# SCH_host-rev-2_0_2025-11-23.net
KiCad netlist of a schematic drawn in EasyEDA
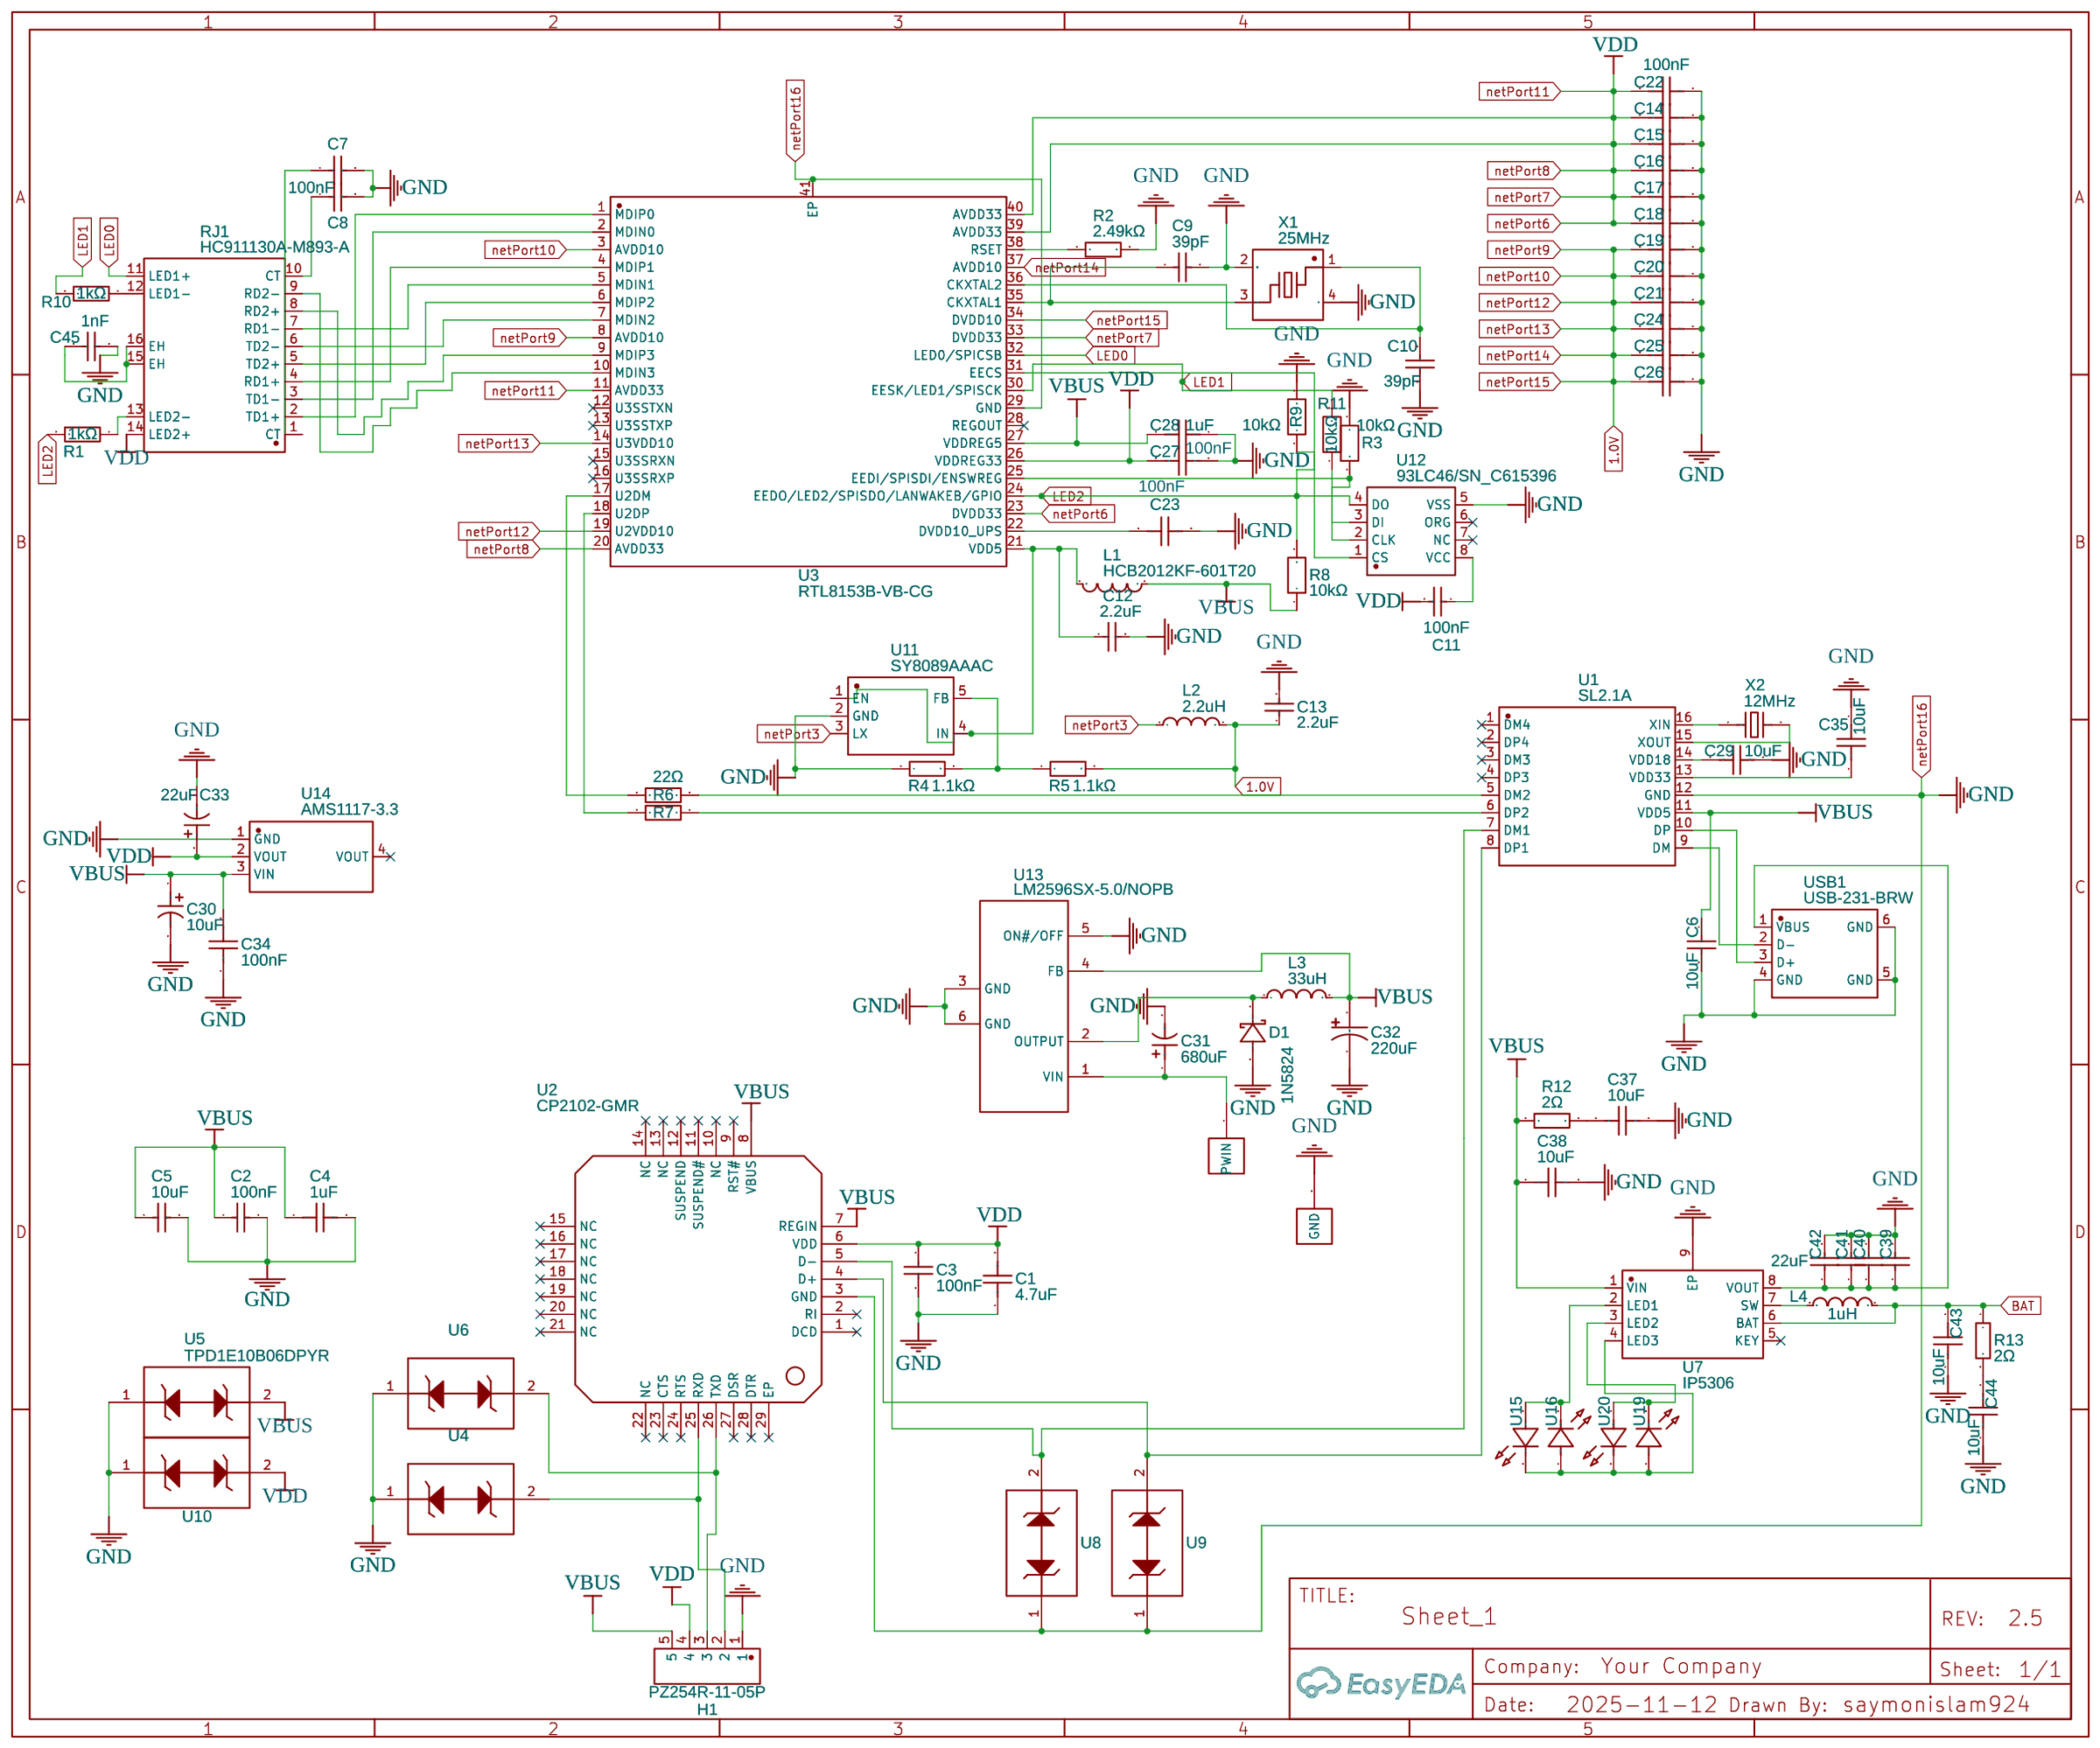
[diagram p0: schematic sheet]

(export (version "E")
  (design (tool "Eeschema 10.0.6"))
  (components
    (comp (ref "C1")
      (value "4.7uF")
      (fields (field (name "Manufacturer Part") "0402X475K100NT") (field (name "Manufacturer") "FH(风华)"))
      (libsource (lib "") (part "0402X475K100NT"))
    )
    (comp (ref "C2")
      (value "100nF")
      (fields (field (name "Manufacturer Part") "0402B104K160NT") (field (name "Manufacturer") "FH(风华)"))
      (libsource (lib "") (part "0402B104K160NT"))
    )
    (comp (ref "C3")
      (value "100nF")
      (fields (field (name "Manufacturer Part") "0402B104K160NT") (field (name "Manufacturer") "FH(风华)"))
      (libsource (lib "") (part "0402B104K160NT_1"))
    )
    (comp (ref "C4")
      (value "1uF")
      (fields (field (name "Manufacturer Part") "0402X105M100NT") (field (name "Manufacturer") "FH(风华)"))
      (libsource (lib "") (part "0402X105M100NT"))
    )
    (comp (ref "C5")
      (value "10uF")
      (fields (field (name "Manufacturer Part") "0603X106K100NT") (field (name "Manufacturer") "FH(风华)"))
      (libsource (lib "") (part "0603X106K100NT"))
    )
    (comp (ref "C6")
      (value "10uF")
      (fields (field (name "Manufacturer Part") "1206B106K160NT") (field (name "Manufacturer") "FH(风华)"))
      (libsource (lib "") (part "1206B106K160NT"))
    )
    (comp (ref "C7")
      (value "100nF")
      (fields (field (name "Manufacturer Part") "0402B104K160NT") (field (name "Manufacturer") "FH(风华)"))
      (libsource (lib "") (part "0402B104K160NT"))
    )
    (comp (ref "C8")
      (value "100nF")
      (fields (field (name "Manufacturer Part") "0402B104K160NT") (field (name "Manufacturer") "FH(风华)"))
      (libsource (lib "") (part "0402B104K160NT"))
    )
    (comp (ref "C9")
      (value "39pF")
      (fields (field (name "Manufacturer Part") "0402CG390J500NT") (field (name "Manufacturer") "FH(风华)"))
      (libsource (lib "") (part "0402CG390J500NT_1"))
    )
    (comp (ref "C10")
      (value "39pF")
      (fields (field (name "Manufacturer Part") "0402CG390J500NT") (field (name "Manufacturer") "FH(风华)"))
      (libsource (lib "") (part "0402CG390J500NT"))
    )
    (comp (ref "C11")
      (value "100nF")
      (fields (field (name "Manufacturer Part") "0402B104J160NT") (field (name "Manufacturer") "FH(风华)"))
      (libsource (lib "") (part "0402B104J160NT"))
    )
    (comp (ref "C12")
      (value "2.2uF")
      (fields (field (name "Manufacturer Part") "0402X225K6R3NT") (field (name "Manufacturer") "FH(风华)"))
      (libsource (lib "") (part "0402X225K6R3NT_1"))
    )
    (comp (ref "C13")
      (value "2.2uF")
      (fields (field (name "Manufacturer Part") "0402X225K6R3NT") (field (name "Manufacturer") "FH(风华)"))
      (libsource (lib "") (part "0402X225K6R3NT"))
    )
    (comp (ref "C14")
      (value "100nF")
      (fields
        (field (name "Manufacturer Part") "CC0402KRX5R6BB104")
        (field (name "Manufacturer") "YAGEO(国巨)")
      )
      (libsource (lib "") (part "CC0402KRX5R6BB104"))
    )
    (comp (ref "C15")
      (value "100nF")
      (fields
        (field (name "Manufacturer Part") "CC0402KRX5R6BB104")
        (field (name "Manufacturer") "YAGEO(国巨)")
      )
      (libsource (lib "") (part "CC0402KRX5R6BB104"))
    )
    (comp (ref "C16")
      (value "100nF")
      (fields
        (field (name "Manufacturer Part") "CC0402KRX5R6BB104")
        (field (name "Manufacturer") "YAGEO(国巨)")
      )
      (libsource (lib "") (part "CC0402KRX5R6BB104"))
    )
    (comp (ref "C17")
      (value "100nF")
      (fields
        (field (name "Manufacturer Part") "CC0402KRX5R6BB104")
        (field (name "Manufacturer") "YAGEO(国巨)")
      )
      (libsource (lib "") (part "CC0402KRX5R6BB104"))
    )
    (comp (ref "C18")
      (value "100nF")
      (fields
        (field (name "Manufacturer Part") "CC0402KRX5R6BB104")
        (field (name "Manufacturer") "YAGEO(国巨)")
      )
      (libsource (lib "") (part "CC0402KRX5R6BB104"))
    )
    (comp (ref "C19")
      (value "100nF")
      (fields
        (field (name "Manufacturer Part") "CC0402KRX5R6BB104")
        (field (name "Manufacturer") "YAGEO(国巨)")
      )
      (libsource (lib "") (part "CC0402KRX5R6BB104"))
    )
    (comp (ref "C20")
      (value "100nF")
      (fields
        (field (name "Manufacturer Part") "CC0402KRX5R6BB104")
        (field (name "Manufacturer") "YAGEO(国巨)")
      )
      (libsource (lib "") (part "CC0402KRX5R6BB104"))
    )
    (comp (ref "C21")
      (value "100nF")
      (fields
        (field (name "Manufacturer Part") "CC0402KRX5R6BB104")
        (field (name "Manufacturer") "YAGEO(国巨)")
      )
      (libsource (lib "") (part "CC0402KRX5R6BB104"))
    )
    (comp (ref "C22")
      (value "100nF")
      (fields
        (field (name "Manufacturer Part") "CC0402KRX5R6BB104")
        (field (name "Manufacturer") "YAGEO(国巨)")
      )
      (libsource (lib "") (part "CC0402KRX5R6BB104"))
    )
    (comp (ref "C23")
      (value "100nF")
      (fields
        (field (name "Manufacturer Part") "CC0402KRX5R6BB104")
        (field (name "Manufacturer") "YAGEO(国巨)")
      )
      (libsource (lib "") (part "CC0402KRX5R6BB104"))
    )
    (comp (ref "C24")
      (value "100nF")
      (fields
        (field (name "Manufacturer Part") "CC0402KRX5R6BB104")
        (field (name "Manufacturer") "YAGEO(国巨)")
      )
      (libsource (lib "") (part "CC0402KRX5R6BB104"))
    )
    (comp (ref "C25")
      (value "100nF")
      (fields
        (field (name "Manufacturer Part") "CC0402KRX5R6BB104")
        (field (name "Manufacturer") "YAGEO(国巨)")
      )
      (libsource (lib "") (part "CC0402KRX5R6BB104"))
    )
    (comp (ref "C26")
      (value "100nF")
      (fields
        (field (name "Manufacturer Part") "CC0402KRX5R6BB104")
        (field (name "Manufacturer") "YAGEO(国巨)")
      )
      (libsource (lib "") (part "CC0402KRX5R6BB104"))
    )
    (comp (ref "C27")
      (value "100nF")
      (fields
        (field (name "Manufacturer Part") "CC0402KRX5R6BB104")
        (field (name "Manufacturer") "YAGEO(国巨)")
      )
      (libsource (lib "") (part "CC0402KRX5R6BB104"))
    )
    (comp (ref "C28")
      (value "1uF")
      (fields (field (name "Manufacturer Part") "0402X105K100NT") (field (name "Manufacturer") "FH(风华)"))
      (libsource (lib "") (part "0402X105K100NT"))
    )
    (comp (ref "C29")
      (value "10uF")
      (fields (field (name "Manufacturer Part") "0402X106M6R3NT") (field (name "Manufacturer") "FH(风华)"))
      (libsource (lib "") (part "0402X106M6R3NT_2"))
    )
    (comp (ref "C30")
      (value "10uF")
      (fields
        (field (name "Manufacturer Part") "RVT1E100M0405 10UF 25V")
        (field (name "Manufacturer") "DMBJ(振宝佳)")
      )
      (libsource (lib "") (part "RVT1E100M0405 10UF 25V"))
    )
    (comp (ref "C31")
      (value "680uF")
      (fields
        (field (name "Manufacturer Part") "GVE1E687M1010CN")
        (field (name "Manufacturer") "ACMECON(鼎容)")
      )
      (libsource (lib "") (part "GVE1E687M1010CN"))
    )
    (comp (ref "C32")
      (value "220uF")
      (fields (field (name "Manufacturer Part") "EEETC1V221P") (field (name "Manufacturer") "PANASONIC(松下)"))
      (libsource (lib "") (part "EEETC1V221P"))
    )
    (comp (ref "C33")
      (value "22uF")
      (fields
        (field (name "Manufacturer Part") "CA45-A-10V-22uF-K")
        (field (name "Manufacturer") "TORCH(火炬)")
      )
      (libsource (lib "") (part "CA45-A-10V-22μF-K"))
    )
    (comp (ref "C34")
      (value "100nF")
      (fields
        (field (name "Manufacturer Part") "CT41G-0805-2X1-50V-0.1uF-M(N)")
        (field (name "Manufacturer") "TORCH(火炬)")
      )
      (libsource (lib "") (part "CT41G-0805-2X1-50V-0.1μF-M(N)"))
    )
    (comp (ref "C35")
      (value "10uF")
      (fields (field (name "Manufacturer Part") "0402X106M6R3NT") (field (name "Manufacturer") "FH(风华)"))
      (libsource (lib "") (part "0402X106M6R3NT"))
    )
    (comp (ref "C37")
      (value "10uF")
      (fields (field (name "Manufacturer Part") "0402X106M6R3NT") (field (name "Manufacturer") "FH(风华)"))
      (libsource (lib "") (part "0402X106M6R3NT_2"))
    )
    (comp (ref "C38")
      (value "10uF")
      (fields (field (name "Manufacturer Part") "0402X106M6R3NT") (field (name "Manufacturer") "FH(风华)"))
      (libsource (lib "") (part "0402X106M6R3NT_2"))
    )
    (comp (ref "C39")
      (value "22uF")
      (fields (field (name "Manufacturer Part") "1206X226K100NT") (field (name "Manufacturer") "FH(风华)"))
      (libsource (lib "") (part "1206X226K100NT"))
    )
    (comp (ref "C40")
      (value "22uF")
      (fields (field (name "Manufacturer Part") "1206X226K100NT") (field (name "Manufacturer") "FH(风华)"))
      (libsource (lib "") (part "1206X226K100NT"))
    )
    (comp (ref "C41")
      (value "22uF")
      (fields (field (name "Manufacturer Part") "1206X226K100NT") (field (name "Manufacturer") "FH(风华)"))
      (libsource (lib "") (part "1206X226K100NT"))
    )
    (comp (ref "C42")
      (value "22uF")
      (fields (field (name "Manufacturer Part") "1206X226K100NT") (field (name "Manufacturer") "FH(风华)"))
      (libsource (lib "") (part "1206X226K100NT"))
    )
    (comp (ref "C43")
      (value "10uF")
      (fields (field (name "Manufacturer Part") "0402X106M6R3NT") (field (name "Manufacturer") "FH(风华)"))
      (libsource (lib "") (part "0402X106M6R3NT_1"))
    )
    (comp (ref "C44")
      (value "10uF")
      (fields (field (name "Manufacturer Part") "0402X106M6R3NT") (field (name "Manufacturer") "FH(风华)"))
      (libsource (lib "") (part "0402X106M6R3NT_1"))
    )
    (comp (ref "C45")
      (value "1nF")
      (fields (field (name "Manufacturer Part") "1206B102K202NT") (field (name "Manufacturer") "FH(风华)"))
      (libsource (lib "") (part "1206B102K202NT"))
    )
    (comp (ref "D1")
      (value "1N5824")
      (fields (field (name "Manufacturer") "FUXINSEMI(富芯森美)"))
      (libsource (lib "") (part "1N5824_C7503125"))
    )
    (comp (ref "H1")
      (value "PZ254R-11-05P")
      (fields (field (name "Manufacturer") "XFCN(兴飞)"))
      (libsource (lib "") (part "PZ254R-11-05P"))
    )
    (comp (ref "L1")
      (value "HCB2012KF-601T20")
      (fields (field (name "Manufacturer") "TAI-TECH(台庆)"))
      (libsource (lib "") (part "HCB2012KF-601T20"))
    )
    (comp (ref "L2")
      (value "2.2uH")
      (fields (field (name "Manufacturer Part") "ANR3015T2R2M") (field (name "Manufacturer") "APV(爱普微)"))
      (libsource (lib "") (part "ANR3015T2R2M"))
    )
    (comp (ref "L3")
      (value "33uH")
      (fields (field (name "Manufacturer Part") "SMDRS1275-330N") (field (name "Manufacturer") "SXN(顺翔诺)"))
      (libsource (lib "") (part "SMDRS1275-330N"))
    )
    (comp (ref "L4")
      (value "1uH")
      (fields (field (name "Manufacturer Part") "PRS3015-1R0NT") (field (name "Manufacturer") "FH(风华)"))
      (libsource (lib "") (part "PRS3015-1R0NT"))
    )
    (comp (ref "R1")
      (value "1kΩ")
      (fields (field (name "Manufacturer Part") "RC-02K1001FT") (field (name "Manufacturer") "FH(风华)"))
      (libsource (lib "") (part "RC-02K1001FT"))
    )
    (comp (ref "R2")
      (value "2.49kΩ")
      (fields (field (name "Manufacturer Part") "RC-02K2491FT") (field (name "Manufacturer") "FH(风华)"))
      (libsource (lib "") (part "RC-02K2491FT"))
    )
    (comp (ref "R3")
      (value "10kΩ")
      (fields (field (name "Manufacturer Part") "RC-02K103JT") (field (name "Manufacturer") "FH(风华)"))
      (libsource (lib "") (part "RC-02K103JT"))
    )
    (comp (ref "R4")
      (value "1.1kΩ")
      (fields (field (name "Manufacturer Part") "RC-02K1101FT") (field (name "Manufacturer") "FH(风华)"))
      (libsource (lib "") (part "RC-02K1101FT"))
    )
    (comp (ref "R5")
      (value "1.1kΩ")
      (fields (field (name "Manufacturer Part") "RC-02K1101FT") (field (name "Manufacturer") "FH(风华)"))
      (libsource (lib "") (part "RC-02K1101FT"))
    )
    (comp (ref "R6")
      (value "22Ω")
      (fields (field (name "Manufacturer Part") "RC-02K22R0FT") (field (name "Manufacturer") "FH(风华)"))
      (libsource (lib "") (part "RC-02K22R0FT"))
    )
    (comp (ref "R7")
      (value "22Ω")
      (fields (field (name "Manufacturer Part") "RC-02K22R0FT") (field (name "Manufacturer") "FH(风华)"))
      (libsource (lib "") (part "RC-02K22R0FT"))
    )
    (comp (ref "R8")
      (value "10kΩ")
      (fields (field (name "Manufacturer Part") "RC-02K103JT") (field (name "Manufacturer") "FH(风华)"))
      (libsource (lib "") (part "RC-02K103JT"))
    )
    (comp (ref "R9")
      (value "10kΩ")
      (fields (field (name "Manufacturer Part") "RC-02K103JT") (field (name "Manufacturer") "FH(风华)"))
      (libsource (lib "") (part "RC-02K103JT"))
    )
    (comp (ref "R10")
      (value "1kΩ")
      (fields (field (name "Manufacturer Part") "RC-02K1001FT") (field (name "Manufacturer") "FH(风华)"))
      (libsource (lib "") (part "RC-02K1001FT"))
    )
    (comp (ref "R11")
      (value "10kΩ")
      (fields (field (name "Manufacturer Part") "RC-02K103JT") (field (name "Manufacturer") "FH(风华)"))
      (libsource (lib "") (part "RC-02K103JT"))
    )
    (comp (ref "R12")
      (value "2Ω")
      (fields (field (name "Manufacturer Part") "RS-03L2R00FT") (field (name "Manufacturer") "FH(风华)"))
      (libsource (lib "") (part "RS-03L2R00FT_1"))
    )
    (comp (ref "R13")
      (value "2Ω")
      (fields (field (name "Manufacturer Part") "RS-03L2R00FT") (field (name "Manufacturer") "FH(风华)"))
      (libsource (lib "") (part "RS-03L2R00FT"))
    )
    (comp (ref "RJ1")
      (value "HC911130A-M893-A")
      (fields
        (field (name "Manufacturer Part") "HC612601A-M893-A")
        (field (name "Manufacturer") "HCTL(华灿天禄)")
      )
      (libsource (lib "") (part "HC911130A-M893-A"))
    )
    (comp (ref "U1")
      (value "SL2.1A")
      (fields (field (name "Manufacturer") "CoreChips(和芯润德)"))
      (libsource (lib "") (part "SL2.1A"))
    )
    (comp (ref "U2")
      (value "CP2102-GMR")
      (fields (field (name "Manufacturer") "SKYWORKS/SILICON LABS(芯科)"))
      (libsource (lib "") (part "CP2102-GMR"))
    )
    (comp (ref "U3")
      (value "RTL8153B-VB-CG")
      (fields (field (name "Manufacturer") "REALTEK(瑞昱)"))
      (libsource (lib "") (part "RTL8153B-VB-CG"))
    )
    (comp (ref "U4")
      (value "TPD1E10B06DPYR")
      (fields (field (name "Manufacturer") "TI(德州仪器)"))
      (libsource (lib "") (part "TPD1E10B06DPYR"))
    )
    (comp (ref "U5")
      (value "TPD1E10B06DPYR")
      (fields (field (name "Manufacturer") "TI(德州仪器)"))
      (libsource (lib "") (part "TPD1E10B06DPYR"))
    )
    (comp (ref "U6")
      (value "TPD1E10B06DPYR")
      (fields (field (name "Manufacturer") "TI(德州仪器)"))
      (libsource (lib "") (part "TPD1E10B06DPYR"))
    )
    (comp (ref "U7")
      (value "IP5306")
      (fields (field (name "Manufacturer") "INJOINIC(英集芯)"))
      (libsource (lib "") (part "IP5306"))
    )
    (comp (ref "U8")
      (value "TPD1E10B06DPYR")
      (fields (field (name "Manufacturer") "TI(德州仪器)"))
      (libsource (lib "") (part "TPD1E10B06DPYR_1"))
    )
    (comp (ref "U9")
      (value "TPD1E10B06DPYR")
      (fields (field (name "Manufacturer") "TI(德州仪器)"))
      (libsource (lib "") (part "TPD1E10B06DPYR_1"))
    )
    (comp (ref "U10")
      (value "TPD1E10B06DPYR")
      (fields (field (name "Manufacturer") "TI(德州仪器)"))
      (libsource (lib "") (part "TPD1E10B06DPYR"))
    )
    (comp (ref "U11")
      (value "SY8089AAAC")
      (fields (field (name "Manufacturer") "Silergy(矽力杰)"))
      (libsource (lib "") (part "SY8089AAAC"))
    )
    (comp (ref "U12")
      (value "93LC46/SN_C615396")
      (fields (field (name "Manufacturer Part") "93LC46/SN") (field (name "Manufacturer") "MICROCHIP(美国微芯)"))
      (libsource (lib "") (part "93LC46/SN_C615396"))
    )
    (comp (ref "U13")
      (value "LM2596SX-5.0/NOPB")
      (fields (field (name "Manufacturer") "TI(德州仪器)"))
      (libsource (lib "") (part "LM2596SX-5.0/NOPB"))
    )
    (comp (ref "U14")
      (value "AMS1117-3.3")
      (fields (field (name "Manufacturer") "AMS"))
      (libsource (lib "") (part "AMS1117-3.3"))
    )
    (comp (ref "U15")
      (value "XL-3216UWC")
      (fields (field (name "Manufacturer") "XINGLIGHT(成兴光)"))
      (libsource (lib "") (part "XL-3216UWC_1"))
    )
    (comp (ref "U16")
      (value "XL-3216UWC")
      (fields (field (name "Manufacturer") "XINGLIGHT(成兴光)"))
      (libsource (lib "") (part "XL-3216UWC"))
    )
    (comp (ref "U19")
      (value "XL-3216UWC")
      (fields (field (name "Manufacturer") "XINGLIGHT(成兴光)"))
      (libsource (lib "") (part "XL-3216UWC"))
    )
    (comp (ref "U20")
      (value "XL-3216UWC")
      (fields (field (name "Manufacturer") "XINGLIGHT(成兴光)"))
      (libsource (lib "") (part "XL-3216UWC_1"))
    )
    (comp (ref "U24") (value "Test-Pad") (libsource (lib "") (part "Test-Pad")))
    (comp (ref "U25") (value "Test-Pad") (libsource (lib "") (part "Test-Pad_1")))
    (comp (ref "USB1")
      (value "USB-231-BRW")
      (fields (field (name "Manufacturer") "XUNPU(讯普)"))
      (libsource (lib "") (part "USB-231-BRW"))
    )
    (comp (ref "X1")
      (value "25MHz")
      (fields
        (field (name "Manufacturer Part") "XXHCCLNANF-25.000000")
        (field (name "Manufacturer") "TAITIEN(泰艺电子)")
      )
      (libsource (lib "") (part "XXHCCLNANF-25.000000"))
    )
    (comp (ref "X2")
      (value "12MHz")
      (fields
        (field (name "Manufacturer Part") "S47SMD12.000M20PF20R30B3")
        (field (name "Manufacturer") "SOSET(索斯特)")
      )
      (libsource (lib "") (part "S47SMD12.000M20PF20R30B3"))
    )
  )
  (nets
    (net (code "1") (name "1.0V") (class "Default")
      (node (ref "C13") (pin "1") (pinfunction "1_1") (pintype "input"))
      (node (ref "C19") (pin "1") (pinfunction "1_1") (pintype "unspecified"))
      (node (ref "C20") (pin "1") (pinfunction "1_1") (pintype "unspecified"))
      (node (ref "C21") (pin "1") (pinfunction "1_1") (pintype "unspecified"))
      (node (ref "C24") (pin "1") (pinfunction "1_1") (pintype "unspecified"))
      (node (ref "C25") (pin "1") (pinfunction "1_1") (pintype "unspecified"))
      (node (ref "C26") (pin "1") (pinfunction "1_1") (pintype "unspecified"))
      (node (ref "L2") (pin "2") (pinfunction "2_2") (pintype "unspecified"))
      (node (ref "R5") (pin "2") (pinfunction "2_2") (pintype "unspecified"))
      (node (ref "U3") (pin "14") (pinfunction "U3VDD10_14") (pintype "unspecified"))
      (node (ref "U3") (pin "19") (pinfunction "U2VDD10_19") (pintype "unspecified"))
      (node (ref "U3") (pin "3") (pinfunction "AVDD10_3") (pintype "unspecified"))
      (node (ref "U3") (pin "34") (pinfunction "DVDD10_34") (pintype "unspecified"))
      (node (ref "U3") (pin "37") (pinfunction "AVDD10_37") (pintype "unspecified"))
      (node (ref "U3") (pin "8") (pinfunction "AVDD10_8") (pintype "unspecified"))
    )
    (net (code "2") (name "BAT") (class "Default")
      (node (ref "C43") (pin "2") (pinfunction "2_2") (pintype "unspecified"))
      (node (ref "L4") (pin "1") (pinfunction "1_1") (pintype "unspecified"))
      (node (ref "R13") (pin "1") (pinfunction "1_1") (pintype "unspecified"))
      (node (ref "U7") (pin "6") (pinfunction "BAT_6") (pintype "unspecified"))
    )
    (net (code "3") (name "LED0") (class "Default")
      (node (ref "RJ1") (pin "11") (pinfunction "LED1+_11") (pintype "unspecified"))
      (node (ref "U3") (pin "32") (pinfunction "LED0/SPICSB_32") (pintype "unspecified"))
    )
    (net (code "4") (name "LED1") (class "Default")
      (node (ref "R10") (pin "2") (pinfunction "2_2") (pintype "unspecified"))
      (node (ref "R11") (pin "2") (pinfunction "2_2") (pintype "unspecified"))
      (node (ref "U3") (pin "30") (pinfunction "EESK/LED1/SPISCK_30") (pintype "unspecified"))
    )
    (net (code "5") (name "LED2") (class "Default")
      (node (ref "R1") (pin "2") (pinfunction "2_2") (pintype "unspecified"))
      (node (ref "R8") (pin "2") (pinfunction "2_2") (pintype "unspecified"))
      (node (ref "R9") (pin "1") (pinfunction "1_1") (pintype "unspecified"))
      (node (ref "U12") (pin "4") (pinfunction "DO_4") (pintype "unspecified"))
      (node (ref "U3") (pin "24") (pinfunction "EEDO/LED2/SPISDO/LANWAKEB/GPIO_24") (pintype "unspecified"))
    )
    (net (code "6") (name "Net-(C7-Pad1)") (class "Default")
      (node (ref "C7") (pin "1") (pinfunction "1_1") (pintype "input"))
      (node (ref "RJ1") (pin "1") (pinfunction "CT_1") (pintype "unspecified"))
    )
    (net (code "7") (name "Net-(C8-Pad1)") (class "Default")
      (node (ref "C8") (pin "1") (pinfunction "1_1") (pintype "input"))
      (node (ref "RJ1") (pin "10") (pinfunction "CT_10") (pintype "unspecified"))
    )
    (net (code "8") (name "Net-(C37-Pad2)") (class "Default")
      (node (ref "C37") (pin "2") (pinfunction "2_2") (pintype "unspecified"))
      (node (ref "R12") (pin "2") (pinfunction "2_2") (pintype "unspecified"))
    )
    (net (code "9") (name "Net-(C44-Pad2)") (class "Default")
      (node (ref "C44") (pin "2") (pinfunction "2_2") (pintype "unspecified"))
      (node (ref "R13") (pin "2") (pinfunction "2_2") (pintype "unspecified"))
    )
    (net (code "10") (name "Net-(C45-Pad1)") (class "Default")
      (node (ref "C45") (pin "1") (pinfunction "1_1") (pintype "input"))
      (node (ref "RJ1") (pin "15") (pinfunction "EH_15") (pintype "unspecified"))
      (node (ref "RJ1") (pin "16") (pinfunction "EH_16") (pintype "unspecified"))
    )
    (net (code "11") (name "Net-(D1-K)") (class "Default")
      (node (ref "D1") (pin "1") (pinfunction "K_1") (pintype "unspecified"))
      (node (ref "L3") (pin "1") (pinfunction "1_1") (pintype "unspecified"))
      (node (ref "U13") (pin "2") (pinfunction "OUTPUT_2") (pintype "unspecified"))
    )
    (net (code "12") (name "Net-(RJ1-LED1-)") (class "Default")
      (node (ref "R10") (pin "1") (pinfunction "1_1") (pintype "unspecified"))
      (node (ref "RJ1") (pin "12") (pinfunction "LED1-_12") (pintype "unspecified"))
    )
    (net (code "13") (name "Net-(RJ1-LED2-)") (class "Default")
      (node (ref "R1") (pin "1") (pinfunction "1_1") (pintype "unspecified"))
      (node (ref "RJ1") (pin "13") (pinfunction "LED2-_13") (pintype "unspecified"))
    )
    (net (code "14") (name "Net-(RJ1-RD1+)") (class "Default")
      (node (ref "RJ1") (pin "4") (pinfunction "RD1+_4") (pintype "unspecified"))
      (node (ref "U3") (pin "4") (pinfunction "MDIP1_4") (pintype "unspecified"))
    )
    (net (code "15") (name "Net-(RJ1-RD1-)") (class "Default")
      (node (ref "RJ1") (pin "7") (pinfunction "RD1-_7") (pintype "unspecified"))
      (node (ref "U3") (pin "5") (pinfunction "MDIN1_5") (pintype "unspecified"))
    )
    (net (code "16") (name "Net-(RJ1-RD2+)") (class "Default")
      (node (ref "RJ1") (pin "8") (pinfunction "RD2+_8") (pintype "unspecified"))
      (node (ref "U3") (pin "9") (pinfunction "MDIP3_9") (pintype "unspecified"))
    )
    (net (code "17") (name "Net-(RJ1-RD2-)") (class "Default")
      (node (ref "RJ1") (pin "9") (pinfunction "RD2-_9") (pintype "unspecified"))
      (node (ref "U3") (pin "10") (pinfunction "MDIN3_10") (pintype "unspecified"))
    )
    (net (code "18") (name "Net-(RJ1-TD1+)") (class "Default")
      (node (ref "RJ1") (pin "2") (pinfunction "TD1+_2") (pintype "unspecified"))
      (node (ref "U3") (pin "1") (pinfunction "MDIP0_1") (pintype "unspecified"))
    )
    (net (code "19") (name "Net-(RJ1-TD1-)") (class "Default")
      (node (ref "RJ1") (pin "3") (pinfunction "TD1-_3") (pintype "unspecified"))
      (node (ref "U3") (pin "2") (pinfunction "MDIN0_2") (pintype "unspecified"))
    )
    (net (code "20") (name "Net-(RJ1-TD2+)") (class "Default")
      (node (ref "RJ1") (pin "5") (pinfunction "TD2+_5") (pintype "unspecified"))
      (node (ref "U3") (pin "6") (pinfunction "MDIP2_6") (pintype "unspecified"))
    )
    (net (code "21") (name "Net-(RJ1-TD2-)") (class "Default")
      (node (ref "RJ1") (pin "6") (pinfunction "TD2-_6") (pintype "unspecified"))
      (node (ref "U3") (pin "7") (pinfunction "MDIN2_7") (pintype "unspecified"))
    )
    (net (code "22") (name "Net-(U1-DM)") (class "Default")
      (node (ref "U1") (pin "9") (pinfunction "DM_9") (pintype "unspecified"))
      (node (ref "USB1") (pin "2") (pinfunction "D-_2") (pintype "unspecified"))
    )
    (net (code "23") (name "Net-(U1-DM1)") (class "Default")
      (node (ref "U1") (pin "7") (pinfunction "DM1_7") (pintype "unspecified"))
      (node (ref "U2") (pin "5") (pinfunction "D-_5") (pintype "unspecified"))
      (node (ref "U8") (pin "2") (pintype "bidirectional"))
    )
    (net (code "24") (name "Net-(U1-DM2)") (class "Default")
      (node (ref "R6") (pin "1") (pinfunction "1_1") (pintype "unspecified"))
      (node (ref "U1") (pin "5") (pinfunction "DM2_5") (pintype "unspecified"))
    )
    (net (code "25") (name "Net-(U1-DP)") (class "Default")
      (node (ref "U1") (pin "10") (pinfunction "DP_10") (pintype "unspecified"))
      (node (ref "USB1") (pin "3") (pinfunction "D+_3") (pintype "unspecified"))
    )
    (net (code "26") (name "Net-(U1-DP1)") (class "Default")
      (node (ref "U1") (pin "8") (pinfunction "DP1_8") (pintype "unspecified"))
      (node (ref "U2") (pin "4") (pinfunction "D+_4") (pintype "unspecified"))
      (node (ref "U9") (pin "2") (pintype "bidirectional"))
    )
    (net (code "27") (name "Net-(U1-DP2)") (class "Default")
      (node (ref "R7") (pin "1") (pinfunction "1_1") (pintype "unspecified"))
      (node (ref "U1") (pin "6") (pinfunction "DP2_6") (pintype "unspecified"))
    )
    (net (code "28") (name "Net-(U1-VDD18)") (class "Default")
      (node (ref "C29") (pin "2") (pinfunction "2_2") (pintype "unspecified"))
      (node (ref "U1") (pin "14") (pinfunction "VDD18_14") (pintype "unspecified"))
    )
    (net (code "29") (name "Net-(U1-VDD33)") (class "Default")
      (node (ref "C35") (pin "2") (pinfunction "2_2") (pintype "unspecified"))
      (node (ref "U1") (pin "13") (pinfunction "VDD33_13") (pintype "unspecified"))
    )
    (net (code "30") (name "Net-(U1-XIN)") (class "Default")
      (node (ref "U1") (pin "16") (pinfunction "XIN_16") (pintype "unspecified"))
      (node (ref "X2") (pin "1") (pinfunction "1_1") (pintype "input"))
    )
    (net (code "31") (name "Net-(U1-XOUT)") (class "Default")
      (node (ref "U1") (pin "15") (pinfunction "XOUT_15") (pintype "unspecified"))
      (node (ref "X2") (pin "2") (pinfunction "2_2") (pintype "input"))
    )
    (net (code "32") (name "Net-(U2-RXD)") (class "Default")
      (node (ref "H1") (pin "2") (pinfunction "2_2") (pintype "unspecified"))
      (node (ref "U2") (pin "25") (pinfunction "RXD_25") (pintype "unspecified"))
      (node (ref "U4") (pin "2") (pintype "bidirectional"))
    )
    (net (code "33") (name "Net-(U2-TXD)") (class "Default")
      (node (ref "H1") (pin "3") (pinfunction "3_3") (pintype "unspecified"))
      (node (ref "U2") (pin "26") (pinfunction "TXD_26") (pintype "unspecified"))
      (node (ref "U6") (pin "2") (pintype "bidirectional"))
    )
    (net (code "34") (name "Net-(U3-CKXTAL1)") (class "Default")
      (node (ref "C9") (pin "1") (pinfunction "1_1") (pintype "input"))
      (node (ref "U3") (pin "35") (pinfunction "CKXTAL1_35") (pintype "unspecified"))
      (node (ref "X1") (pin "3") (pinfunction "3_3") (pintype "input"))
    )
    (net (code "35") (name "Net-(U3-CKXTAL2)") (class "Default")
      (node (ref "C10") (pin "1") (pinfunction "1_1") (pintype "input"))
      (node (ref "U3") (pin "36") (pinfunction "CKXTAL2_36") (pintype "unspecified"))
      (node (ref "X1") (pin "1") (pinfunction "1_1") (pintype "input"))
    )
    (net (code "36") (name "Net-(U3-DVDD10_UPS)") (class "Default")
      (node (ref "C23") (pin "1") (pinfunction "1_1") (pintype "unspecified"))
      (node (ref "U3") (pin "22") (pinfunction "DVDD10_UPS_22") (pintype "unspecified"))
    )
    (net (code "37") (name "Net-(U3-RSET)") (class "Default")
      (node (ref "R2") (pin "1") (pinfunction "1_1") (pintype "unspecified"))
      (node (ref "U3") (pin "38") (pinfunction "RSET_38") (pintype "unspecified"))
    )
    (net (code "38") (name "Net-(U3-U2DM)") (class "Default")
      (node (ref "R6") (pin "2") (pinfunction "2_2") (pintype "unspecified"))
      (node (ref "U3") (pin "17") (pinfunction "U2DM_17") (pintype "unspecified"))
    )
    (net (code "39") (name "Net-(U3-U2DP)") (class "Default")
      (node (ref "R7") (pin "2") (pinfunction "2_2") (pintype "unspecified"))
      (node (ref "U3") (pin "18") (pinfunction "U2DP_18") (pintype "unspecified"))
    )
    (net (code "40") (name "Net-(U7-SW)") (class "Default")
      (node (ref "L4") (pin "2") (pinfunction "2_2") (pintype "unspecified"))
      (node (ref "U7") (pin "7") (pinfunction "SW_7") (pintype "unspecified"))
    )
    (net (code "41") (name "Net-(U7-VOUT)") (class "Default")
      (node (ref "C39") (pin "1") (pinfunction "1_1") (pintype "input"))
      (node (ref "C40") (pin "1") (pinfunction "1_1") (pintype "input"))
      (node (ref "C41") (pin "1") (pinfunction "1_1") (pintype "input"))
      (node (ref "C42") (pin "1") (pinfunction "1_1") (pintype "input"))
      (node (ref "U7") (pin "8") (pinfunction "VOUT_8") (pintype "unspecified"))
      (node (ref "USB1") (pin "1") (pinfunction "VBUS_1") (pintype "unspecified"))
    )
    (net (code "42") (name "Net-(U11-EN)") (class "Default")
      (node (ref "C12") (pin "1") (pinfunction "1_1") (pintype "input"))
      (node (ref "L1") (pin "2") (pinfunction "2_2") (pintype "unspecified"))
      (node (ref "U11") (pin "1") (pinfunction "EN_1") (pintype "unspecified"))
      (node (ref "U11") (pin "4") (pinfunction "IN_4") (pintype "unspecified"))
      (node (ref "U3") (pin "21") (pinfunction "VDD5_21") (pintype "unspecified"))
    )
    (net (code "43") (name "Net-(U11-FB)") (class "Default")
      (node (ref "R4") (pin "2") (pinfunction "2_2") (pintype "unspecified"))
      (node (ref "R5") (pin "1") (pinfunction "1_1") (pintype "unspecified"))
      (node (ref "U11") (pin "5") (pinfunction "FB_5") (pintype "unspecified"))
    )
    (net (code "44") (name "Net-(U12-CLK)") (class "Default")
      (node (ref "R11") (pin "1") (pinfunction "1_1") (pintype "unspecified"))
      (node (ref "U12") (pin "2") (pinfunction "CLK_2") (pintype "unspecified"))
    )
    (net (code "45") (name "Net-(U12-CS)") (class "Default")
      (node (ref "U12") (pin "1") (pinfunction "CS_1") (pintype "unspecified"))
      (node (ref "U3") (pin "31") (pinfunction "EECS_31") (pintype "unspecified"))
    )
    (net (code "46") (name "Net-(U12-DI)") (class "Default")
      (node (ref "R3") (pin "1") (pinfunction "1_1") (pintype "unspecified"))
      (node (ref "U12") (pin "3") (pinfunction "DI_3") (pintype "unspecified"))
      (node (ref "U3") (pin "25") (pinfunction "EEDI/SPISDI/ENSWREG_25") (pintype "unspecified"))
    )
    (net (code "47") (name "Net-(U12-VCC)") (class "Default")
      (node (ref "C11") (pin "1") (pinfunction "1_1") (pintype "input"))
      (node (ref "U12") (pin "8") (pinfunction "VCC_8") (pintype "unspecified"))
    )
    (net (code "48") (name "Net-(U13-VIN)") (class "Default")
      (node (ref "C31") (pin "1") (pinfunction "1_1") (pintype "input"))
      (node (ref "U13") (pin "1") (pinfunction "VIN_1") (pintype "unspecified"))
      (node (ref "U24") (pin "1") (pinfunction "PWIN_1") (pintype "unspecified"))
    )
    (net (code "49") (name "Net-(U15-A)") (class "Default")
      (node (ref "U15") (pin "1") (pinfunction "A_1") (pintype "unspecified"))
      (node (ref "U16") (pin "2") (pinfunction "K_2") (pintype "unspecified"))
      (node (ref "U7") (pin "2") (pinfunction "LED1_2") (pintype "unspecified"))
    )
    (net (code "50") (name "Net-(U15-K)") (class "Default")
      (node (ref "U15") (pin "2") (pinfunction "K_2") (pintype "unspecified"))
      (node (ref "U16") (pin "1") (pinfunction "A_1") (pintype "unspecified"))
      (node (ref "U19") (pin "1") (pinfunction "A_1") (pintype "unspecified"))
      (node (ref "U20") (pin "2") (pinfunction "K_2") (pintype "unspecified"))
      (node (ref "U7") (pin "4") (pinfunction "LED3_4") (pintype "unspecified"))
    )
    (net (code "51") (name "Net-(U19-K)") (class "Default")
      (node (ref "U19") (pin "2") (pinfunction "K_2") (pintype "unspecified"))
      (node (ref "U20") (pin "1") (pinfunction "A_1") (pintype "unspecified"))
      (node (ref "U7") (pin "3") (pinfunction "LED2_3") (pintype "unspecified"))
    )
    (net (code "52") (name "VBUS") (class "Default")
      (node (ref "C2") (pin "1") (pinfunction "1_1") (pintype "input"))
      (node (ref "C28") (pin "2") (pinfunction "2_2") (pintype "unspecified"))
      (node (ref "C30") (pin "1") (pinfunction "1_1") (pintype "input"))
      (node (ref "C32") (pin "1") (pinfunction "1_1") (pintype "unspecified"))
      (node (ref "C34") (pin "1") (pinfunction "1_1") (pintype "unspecified"))
      (node (ref "C38") (pin "2") (pinfunction "2_2") (pintype "unspecified"))
      (node (ref "C4") (pin "1") (pinfunction "1_1") (pintype "unspecified"))
      (node (ref "C5") (pin "1") (pinfunction "1_1") (pintype "input"))
      (node (ref "C6") (pin "1") (pinfunction "1_1") (pintype "input"))
      (node (ref "H1") (pin "5") (pinfunction "5_5") (pintype "unspecified"))
      (node (ref "L1") (pin "1") (pinfunction "1_1") (pintype "unspecified"))
      (node (ref "L3") (pin "2") (pinfunction "2_2") (pintype "unspecified"))
      (node (ref "R12") (pin "1") (pinfunction "1_1") (pintype "unspecified"))
      (node (ref "R8") (pin "1") (pinfunction "1_1") (pintype "unspecified"))
      (node (ref "U1") (pin "11") (pinfunction "VDD5_11") (pintype "unspecified"))
      (node (ref "U13") (pin "4") (pinfunction "FB_4") (pintype "unspecified"))
      (node (ref "U14") (pin "3") (pinfunction "VIN_3") (pintype "unspecified"))
      (node (ref "U2") (pin "7") (pinfunction "REGIN_7") (pintype "unspecified"))
      (node (ref "U2") (pin "8") (pinfunction "VBUS_8") (pintype "unspecified"))
      (node (ref "U3") (pin "27") (pinfunction "VDDREG5_27") (pintype "unspecified"))
      (node (ref "U5") (pin "2") (pintype "bidirectional"))
      (node (ref "U7") (pin "1") (pinfunction "VIN_1") (pintype "unspecified"))
    )
    (net (code "53") (name "netPort3") (class "Default")
      (node (ref "L2") (pin "1") (pinfunction "1_1") (pintype "unspecified"))
      (node (ref "U11") (pin "3") (pinfunction "LX_3") (pintype "unspecified"))
    )
    (net (code "54") (name "netPort11") (class "Default")
      (node (ref "C1") (pin "2") (pinfunction "2_2") (pintype "unspecified"))
      (node (ref "C11") (pin "2") (pinfunction "2_2") (pintype "input"))
      (node (ref "C14") (pin "1") (pinfunction "1_1") (pintype "unspecified"))
      (node (ref "C15") (pin "1") (pinfunction "1_1") (pintype "unspecified"))
      (node (ref "C16") (pin "1") (pinfunction "1_1") (pintype "unspecified"))
      (node (ref "C17") (pin "1") (pinfunction "1_1") (pintype "unspecified"))
      (node (ref "C18") (pin "1") (pinfunction "1_1") (pintype "unspecified"))
      (node (ref "C22") (pin "1") (pinfunction "1_1") (pintype "unspecified"))
      (node (ref "C27") (pin "1") (pinfunction "1_1") (pintype "unspecified"))
      (node (ref "C3") (pin "1") (pinfunction "1_1") (pintype "input"))
      (node (ref "C33") (pin "1") (pinfunction "1_1") (pintype "input"))
      (node (ref "H1") (pin "4") (pinfunction "4_4") (pintype "unspecified"))
      (node (ref "RJ1") (pin "14") (pinfunction "LED2+_14") (pintype "unspecified"))
      (node (ref "U10") (pin "2") (pintype "bidirectional"))
      (node (ref "U14") (pin "2") (pinfunction "VOUT_2") (pintype "unspecified"))
      (node (ref "U2") (pin "6") (pinfunction "VDD_6") (pintype "unspecified"))
      (node (ref "U3") (pin "11") (pinfunction "AVDD33_11") (pintype "unspecified"))
      (node (ref "U3") (pin "20") (pinfunction "AVDD33_20") (pintype "unspecified"))
      (node (ref "U3") (pin "23") (pinfunction "DVDD33_23") (pintype "unspecified"))
      (node (ref "U3") (pin "26") (pinfunction "VDDREG33_26") (pintype "unspecified"))
      (node (ref "U3") (pin "33") (pinfunction "DVDD33_33") (pintype "unspecified"))
      (node (ref "U3") (pin "39") (pinfunction "AVDD33_39") (pintype "unspecified"))
      (node (ref "U3") (pin "40") (pinfunction "AVDD33_40") (pintype "unspecified"))
    )
    (net (code "55") (name "netPort16") (class "Default")
      (node (ref "C1") (pin "1") (pinfunction "1_1") (pintype "unspecified"))
      (node (ref "C10") (pin "2") (pinfunction "2_2") (pintype "input"))
      (node (ref "C12") (pin "2") (pinfunction "2_2") (pintype "input"))
      (node (ref "C13") (pin "2") (pinfunction "2_2") (pintype "input"))
      (node (ref "C14") (pin "2") (pinfunction "2_2") (pintype "unspecified"))
      (node (ref "C15") (pin "2") (pinfunction "2_2") (pintype "unspecified"))
      (node (ref "C16") (pin "2") (pinfunction "2_2") (pintype "unspecified"))
      (node (ref "C17") (pin "2") (pinfunction "2_2") (pintype "unspecified"))
      (node (ref "C18") (pin "2") (pinfunction "2_2") (pintype "unspecified"))
      (node (ref "C19") (pin "2") (pinfunction "2_2") (pintype "unspecified"))
      (node (ref "C2") (pin "2") (pinfunction "2_2") (pintype "input"))
      (node (ref "C20") (pin "2") (pinfunction "2_2") (pintype "unspecified"))
      (node (ref "C21") (pin "2") (pinfunction "2_2") (pintype "unspecified"))
      (node (ref "C22") (pin "2") (pinfunction "2_2") (pintype "unspecified"))
      (node (ref "C23") (pin "2") (pinfunction "2_2") (pintype "unspecified"))
      (node (ref "C24") (pin "2") (pinfunction "2_2") (pintype "unspecified"))
      (node (ref "C25") (pin "2") (pinfunction "2_2") (pintype "unspecified"))
      (node (ref "C26") (pin "2") (pinfunction "2_2") (pintype "unspecified"))
      (node (ref "C27") (pin "2") (pinfunction "2_2") (pintype "unspecified"))
      (node (ref "C28") (pin "1") (pinfunction "1_1") (pintype "unspecified"))
      (node (ref "C29") (pin "1") (pinfunction "1_1") (pintype "unspecified"))
      (node (ref "C3") (pin "2") (pinfunction "2_2") (pintype "input"))
      (node (ref "C30") (pin "2") (pinfunction "2_2") (pintype "input"))
      (node (ref "C31") (pin "2") (pinfunction "2_2") (pintype "input"))
      (node (ref "C32") (pin "2") (pinfunction "2_2") (pintype "unspecified"))
      (node (ref "C33") (pin "2") (pinfunction "2_2") (pintype "input"))
      (node (ref "C34") (pin "2") (pinfunction "2_2") (pintype "unspecified"))
      (node (ref "C35") (pin "1") (pinfunction "1_1") (pintype "unspecified"))
      (node (ref "C37") (pin "1") (pinfunction "1_1") (pintype "unspecified"))
      (node (ref "C38") (pin "1") (pinfunction "1_1") (pintype "unspecified"))
      (node (ref "C39") (pin "2") (pinfunction "2_2") (pintype "input"))
      (node (ref "C4") (pin "2") (pinfunction "2_2") (pintype "unspecified"))
      (node (ref "C40") (pin "2") (pinfunction "2_2") (pintype "input"))
      (node (ref "C41") (pin "2") (pinfunction "2_2") (pintype "input"))
      (node (ref "C42") (pin "2") (pinfunction "2_2") (pintype "input"))
      (node (ref "C43") (pin "1") (pinfunction "1_1") (pintype "unspecified"))
      (node (ref "C44") (pin "1") (pinfunction "1_1") (pintype "unspecified"))
      (node (ref "C45") (pin "2") (pinfunction "2_2") (pintype "input"))
      (node (ref "C5") (pin "2") (pinfunction "2_2") (pintype "input"))
      (node (ref "C6") (pin "2") (pinfunction "2_2") (pintype "input"))
      (node (ref "C7") (pin "2") (pinfunction "2_2") (pintype "input"))
      (node (ref "C8") (pin "2") (pinfunction "2_2") (pintype "input"))
      (node (ref "C9") (pin "2") (pinfunction "2_2") (pintype "input"))
      (node (ref "D1") (pin "2") (pinfunction "A_2") (pintype "unspecified"))
      (node (ref "H1") (pin "1") (pinfunction "1_1") (pintype "unspecified"))
      (node (ref "R2") (pin "2") (pinfunction "2_2") (pintype "unspecified"))
      (node (ref "R3") (pin "2") (pinfunction "2_2") (pintype "unspecified"))
      (node (ref "R4") (pin "1") (pinfunction "1_1") (pintype "unspecified"))
      (node (ref "R9") (pin "2") (pinfunction "2_2") (pintype "unspecified"))
      (node (ref "U1") (pin "12") (pinfunction "GND_12") (pintype "unspecified"))
      (node (ref "U10") (pin "1") (pintype "bidirectional"))
      (node (ref "U11") (pin "2") (pinfunction "GND_2") (pintype "unspecified"))
      (node (ref "U12") (pin "5") (pinfunction "VSS_5") (pintype "unspecified"))
      (node (ref "U13") (pin "3") (pinfunction "GND_3") (pintype "unspecified"))
      (node (ref "U13") (pin "5") (pinfunction "ON#/OFF_5") (pintype "unspecified"))
      (node (ref "U13") (pin "6") (pinfunction "GND_6") (pintype "unspecified"))
      (node (ref "U14") (pin "1") (pinfunction "GND_1") (pintype "unspecified"))
      (node (ref "U2") (pin "3") (pinfunction "GND_3") (pintype "unspecified"))
      (node (ref "U25") (pin "1") (pinfunction "GND_1") (pintype "unspecified"))
      (node (ref "U3") (pin "29") (pinfunction "GND_29") (pintype "unspecified"))
      (node (ref "U3") (pin "41") (pinfunction "EP_41") (pintype "unspecified"))
      (node (ref "U4") (pin "1") (pintype "bidirectional"))
      (node (ref "U5") (pin "1") (pintype "bidirectional"))
      (node (ref "U6") (pin "1") (pintype "bidirectional"))
      (node (ref "U7") (pin "9") (pinfunction "EP_9") (pintype "unspecified"))
      (node (ref "U8") (pin "1") (pintype "bidirectional"))
      (node (ref "U9") (pin "1") (pintype "bidirectional"))
      (node (ref "USB1") (pin "4") (pinfunction "GND_4") (pintype "unspecified"))
      (node (ref "USB1") (pin "5") (pinfunction "GND_5") (pintype "unspecified"))
      (node (ref "USB1") (pin "6") (pinfunction "GND_6") (pintype "unspecified"))
      (node (ref "X1") (pin "2") (pinfunction "GND_2") (pintype "input"))
      (node (ref "X1") (pin "4") (pinfunction "GND_4") (pintype "input"))
    )
    (net (code "56") (name "unconnected-(U1-DM3-Pad3)") (class "Default")
      (node (ref "U1") (pin "3") (pinfunction "DM3_3") (pintype "unspecified+no_connect"))
    )
    (net (code "57") (name "unconnected-(U1-DM4-Pad1)") (class "Default")
      (node (ref "U1") (pin "1") (pinfunction "DM4_1") (pintype "unspecified+no_connect"))
    )
    (net (code "58") (name "unconnected-(U1-DP3-Pad4)") (class "Default")
      (node (ref "U1") (pin "4") (pinfunction "DP3_4") (pintype "unspecified+no_connect"))
    )
    (net (code "59") (name "unconnected-(U1-DP4-Pad2)") (class "Default")
      (node (ref "U1") (pin "2") (pinfunction "DP4_2") (pintype "unspecified+no_connect"))
    )
    (net (code "60") (name "unconnected-(U2-CTS-Pad23)") (class "Default")
      (node (ref "U2") (pin "23") (pinfunction "CTS_23") (pintype "unspecified+no_connect"))
    )
    (net (code "61") (name "unconnected-(U2-DCD-Pad1)") (class "Default")
      (node (ref "U2") (pin "1") (pinfunction "DCD_1") (pintype "unspecified+no_connect"))
    )
    (net (code "62") (name "unconnected-(U2-DSR-Pad27)") (class "Default")
      (node (ref "U2") (pin "27") (pinfunction "DSR_27") (pintype "unspecified+no_connect"))
    )
    (net (code "63") (name "unconnected-(U2-DTR-Pad28)") (class "Default")
      (node (ref "U2") (pin "28") (pinfunction "DTR_28") (pintype "unspecified+no_connect"))
    )
    (net (code "64") (name "unconnected-(U2-EP-Pad29)") (class "Default")
      (node (ref "U2") (pin "29") (pinfunction "EP_29") (pintype "unspecified+no_connect"))
    )
    (net (code "65") (name "unconnected-(U2-NC-Pad10)") (class "Default")
      (node (ref "U2") (pin "10") (pinfunction "NC_10") (pintype "unspecified+no_connect"))
    )
    (net (code "66") (name "unconnected-(U2-NC-Pad13)") (class "Default")
      (node (ref "U2") (pin "13") (pinfunction "NC_13") (pintype "unspecified+no_connect"))
    )
    (net (code "67") (name "unconnected-(U2-NC-Pad14)") (class "Default")
      (node (ref "U2") (pin "14") (pinfunction "NC_14") (pintype "unspecified+no_connect"))
    )
    (net (code "68") (name "unconnected-(U2-NC-Pad15)") (class "Default")
      (node (ref "U2") (pin "15") (pinfunction "NC_15") (pintype "unspecified+no_connect"))
    )
    (net (code "69") (name "unconnected-(U2-NC-Pad16)") (class "Default")
      (node (ref "U2") (pin "16") (pinfunction "NC_16") (pintype "unspecified+no_connect"))
    )
    (net (code "70") (name "unconnected-(U2-NC-Pad17)") (class "Default")
      (node (ref "U2") (pin "17") (pinfunction "NC_17") (pintype "unspecified+no_connect"))
    )
    (net (code "71") (name "unconnected-(U2-NC-Pad18)") (class "Default")
      (node (ref "U2") (pin "18") (pinfunction "NC_18") (pintype "unspecified+no_connect"))
    )
    (net (code "72") (name "unconnected-(U2-NC-Pad19)") (class "Default")
      (node (ref "U2") (pin "19") (pinfunction "NC_19") (pintype "unspecified+no_connect"))
    )
    (net (code "73") (name "unconnected-(U2-NC-Pad20)") (class "Default")
      (node (ref "U2") (pin "20") (pinfunction "NC_20") (pintype "unspecified+no_connect"))
    )
    (net (code "74") (name "unconnected-(U2-NC-Pad21)") (class "Default")
      (node (ref "U2") (pin "21") (pinfunction "NC_21") (pintype "unspecified+no_connect"))
    )
    (net (code "75") (name "unconnected-(U2-NC-Pad22)") (class "Default")
      (node (ref "U2") (pin "22") (pinfunction "NC_22") (pintype "unspecified+no_connect"))
    )
    (net (code "76") (name "unconnected-(U2-RI-Pad2)") (class "Default")
      (node (ref "U2") (pin "2") (pinfunction "RI_2") (pintype "unspecified+no_connect"))
    )
    (net (code "77") (name "unconnected-(U2-RST#-Pad9)") (class "Default")
      (node (ref "U2") (pin "9") (pinfunction "RST#_9") (pintype "unspecified+no_connect"))
    )
    (net (code "78") (name "unconnected-(U2-RTS-Pad24)") (class "Default")
      (node (ref "U2") (pin "24") (pinfunction "RTS_24") (pintype "unspecified+no_connect"))
    )
    (net (code "79") (name "unconnected-(U2-SUSPEND#-Pad11)") (class "Default")
      (node (ref "U2") (pin "11") (pinfunction "SUSPEND#_11") (pintype "unspecified+no_connect"))
    )
    (net (code "80") (name "unconnected-(U2-SUSPEND-Pad12)") (class "Default")
      (node (ref "U2") (pin "12") (pinfunction "SUSPEND_12") (pintype "unspecified+no_connect"))
    )
    (net (code "81") (name "unconnected-(U3-REGOUT-Pad28)") (class "Default")
      (node (ref "U3") (pin "28") (pinfunction "REGOUT_28") (pintype "unspecified+no_connect"))
    )
    (net (code "82") (name "unconnected-(U3-U3SSRXN-Pad15)") (class "Default")
      (node (ref "U3") (pin "15") (pinfunction "U3SSRXN_15") (pintype "unspecified+no_connect"))
    )
    (net (code "83") (name "unconnected-(U3-U3SSRXP-Pad16)") (class "Default")
      (node (ref "U3") (pin "16") (pinfunction "U3SSRXP_16") (pintype "unspecified+no_connect"))
    )
    (net (code "84") (name "unconnected-(U3-U3SSTXN-Pad12)") (class "Default")
      (node (ref "U3") (pin "12") (pinfunction "U3SSTXN_12") (pintype "unspecified+no_connect"))
    )
    (net (code "85") (name "unconnected-(U3-U3SSTXP-Pad13)") (class "Default")
      (node (ref "U3") (pin "13") (pinfunction "U3SSTXP_13") (pintype "unspecified+no_connect"))
    )
    (net (code "86") (name "unconnected-(U7-KEY-Pad5)") (class "Default")
      (node (ref "U7") (pin "5") (pinfunction "KEY_5") (pintype "unspecified+no_connect"))
    )
    (net (code "87") (name "unconnected-(U12-NC-Pad7)") (class "Default")
      (node (ref "U12") (pin "7") (pinfunction "NC_7") (pintype "unspecified+no_connect"))
    )
    (net (code "88") (name "unconnected-(U12-ORG-Pad6)") (class "Default")
      (node (ref "U12") (pin "6") (pinfunction "ORG_6") (pintype "unspecified+no_connect"))
    )
    (net (code "89") (name "unconnected-(U14-VOUT-Pad4)") (class "Default")
      (node (ref "U14") (pin "4") (pinfunction "VOUT_4") (pintype "unspecified+no_connect"))
    )
  )
)
